# M3406-ADJ_3V3.net
KiCad netlist of a schematic drawn in Altium Designer
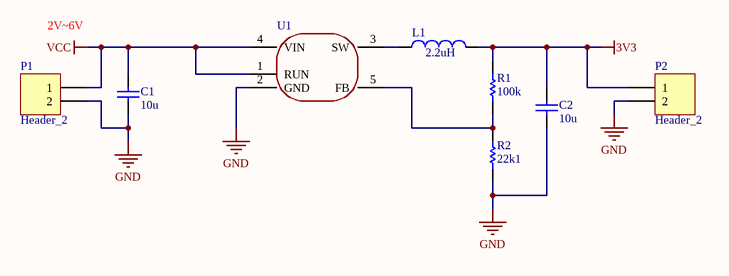
[diagram p0: M3406-ADJ_3V3.SchDoc]

(export (version "E")
  (design (tool "Eeschema 10.0.6"))
  (components
    (comp (ref "C1")
      (value "10u")
      (footprint "CAP 0603_1608")
      (fields
        (field (name "MPN") "GRM188R61E106KA73D")
        (field (name "MANUFACTURER") "Murata")
        (field (name "TOLERANCE") "10%")
      )
      (libsource (lib "std_lib") (part "Capacitor"))
    )
    (comp (ref "C2")
      (value "10u")
      (footprint "CAP 0603_1608")
      (fields
        (field (name "MPN") "GRM188R61E106KA73D")
        (field (name "MANUFACTURER") "Murata")
        (field (name "TOLERANCE") "10%")
      )
      (libsource (lib "std_lib") (part "Capacitor"))
    )
    (comp (ref "L1")
      (value "2.2uH")
      (footprint "IND-SMD_L2.0-W1.6")
      (fields
        (field (name "MPN") "WPN201610U2R2MTY01")
        (field (name "MANUFACTURER") "Sunlord(顺络)")
        (field (name "TOLERANCE") "20%")
      )
      (libsource (lib "std_lib") (part "Inductor"))
    )
    (comp (ref "P1")
      (value "Header_2")
      (footprint "PAD_2.54mmx2")
      (description "SMD，DIP")
      (fields (field (name "MPN") "PAD_2.54MM_2"))
      (libsource (lib "std_lib") (part "Header_2"))
    )
    (comp (ref "P2")
      (value "Header_2")
      (footprint "PAD_2.54mmx2")
      (description "SMD，DIP")
      (fields (field (name "MPN") "PAD_2.54MM_2"))
      (libsource (lib "") (part "Header_2_1"))
    )
    (comp (ref "R1")
      (value "100k")
      (footprint "RES 0402_1005")
      (fields
        (field (name "MPN") "RC0402FR-07100KL")
        (field (name "MANUFACTURER") "Yageo")
        (field (name "TOLERANCE") "1%")
      )
      (libsource (lib "std_lib") (part "Resistor"))
    )
    (comp (ref "R2")
      (value "22k1")
      (footprint "RES 0402_1005")
      (fields
        (field (name "MPN") "RC0402FR-0722K1L")
        (field (name "MANUFACTURER") "Yageo")
        (field (name "TOLERANCE") "1%")
      )
      (libsource (lib "std_lib") (part "Resistor"))
    )
    (comp (ref "U1")
      (value "M3406-ADJ")
      (footprint "SOT-23-5_L3.0-W1.7-P0.95-LS2.8-BR")
      (description "Vin=2V~6V,800mA,DCDC")
      (fields (field (name "MANUFACTURER") "西安航天民芯"))
      (libsource (lib "std_lib") (part "M3406-ADJ"))
    )
  )
  (nets
    (net (code "1") (name "3V3") (class "Default")
      (node (ref "C2") (pin "2") (pinfunction "2_2") (pintype "passive"))
      (node (ref "L1") (pin "2") (pinfunction "2_2") (pintype "passive"))
      (node (ref "P2") (pin "1") (pinfunction "1_1") (pintype "passive"))
      (node (ref "R1") (pin "2") (pinfunction "2_2") (pintype "passive"))
    )
    (net (code "2") (name "GND") (class "Default")
      (node (ref "C1") (pin "1") (pinfunction "1_1") (pintype "passive"))
      (node (ref "C2") (pin "1") (pinfunction "1_1") (pintype "passive"))
      (node (ref "P1") (pin "2") (pinfunction "2_2") (pintype "passive"))
      (node (ref "P2") (pin "2") (pinfunction "2_2") (pintype "passive"))
      (node (ref "R2") (pin "1") (pinfunction "1_1") (pintype "passive"))
      (node (ref "U1") (pin "2") (pinfunction "GND_2") (pintype "passive"))
    )
    (net (code "3") (name "Net-(U1-FB)") (class "Default")
      (node (ref "R1") (pin "1") (pinfunction "1_1") (pintype "passive"))
      (node (ref "R2") (pin "2") (pinfunction "2_2") (pintype "passive"))
      (node (ref "U1") (pin "5") (pinfunction "FB_5") (pintype "passive"))
    )
    (net (code "4") (name "Net-(U1-SW)") (class "Default")
      (node (ref "L1") (pin "1") (pinfunction "1_1") (pintype "passive"))
      (node (ref "U1") (pin "3") (pinfunction "SW_3") (pintype "passive"))
    )
    (net (code "5") (name "VCC") (class "Default")
      (node (ref "C1") (pin "2") (pinfunction "2_2") (pintype "passive"))
      (node (ref "P1") (pin "1") (pinfunction "1_1") (pintype "passive"))
      (node (ref "U1") (pin "1") (pinfunction "RUN_1") (pintype "passive"))
      (node (ref "U1") (pin "4") (pinfunction "VIN_4") (pintype "passive"))
    )
  )
)
